# RTC.net
KiCad netlist of a schematic drawn in Altium Designer
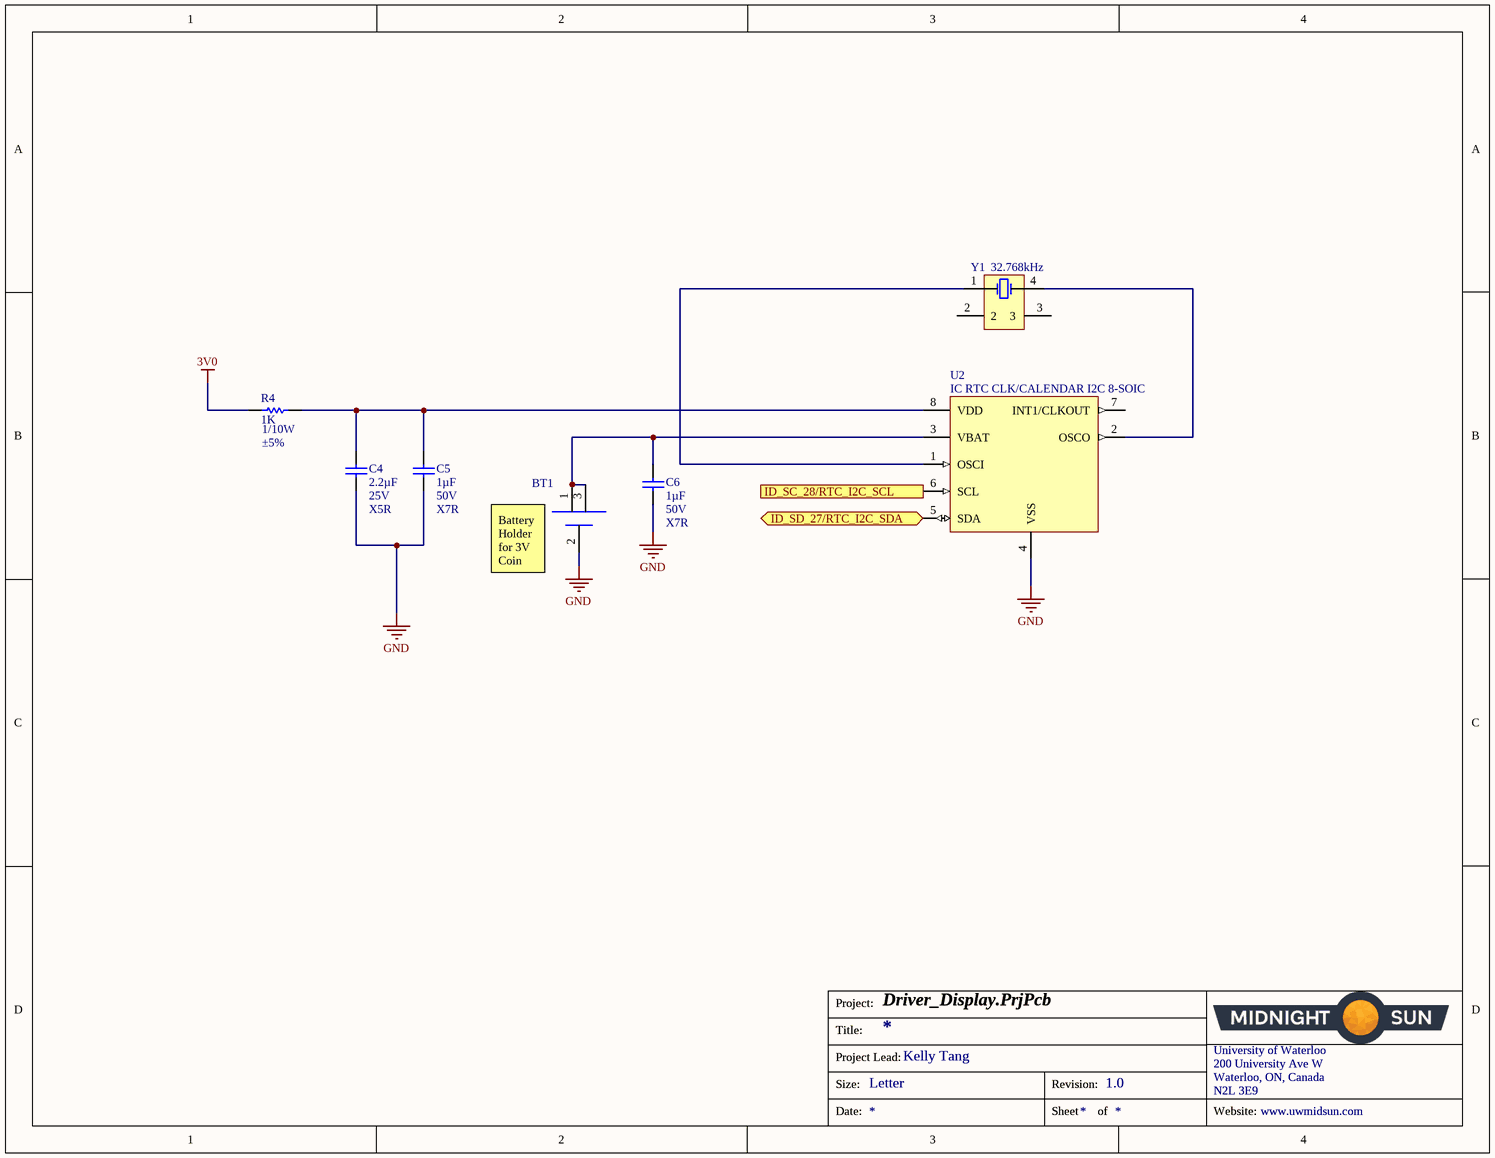
[diagram p0: RTC.SchDoc]

(export (version "E")
  (design (tool "Eeschema 10.0.6"))
  (components
    (comp (ref "BT1")
      (value "HOLDER BATTERY COIN 12MM DIA")
      (footprint "HOLDER COIN CELL 1220 3V")
      (description "Coin cell holder smd")
      (fields
        (field (name "MANUFACTURER") "Keystone Electronics")
        (field (name "MANUFACTURER PART NUMBER") "3000")
      )
      (libsource (lib "Schematic Diagrams") (part "HOLDER BATTERY COIN 12MM DIA"))
    )
    (comp (ref "C4")
      (value "CAP CER 2.2UF 25V 10% X5R 0603")
      (footprint "CAP, 0603")
      (description "2.2µF ±10% 25V Ceramic Capacitor X5R 0603 (1608 Metric)")
      (fields
        (field (name "TOLERANCE") "±10%")
        (field (name "CAPACITANCE") "2.2µF")
        (field (name "VOLTAGE") "25V")
        (field (name "TEMPERATURE COEFFICIENT") "X5R")
      )
      (libsource (lib "Schematic Diagrams") (part "CAP CER 2.2UF 25V 10% X5R 0603"))
    )
    (comp (ref "C5")
      (value "CAP CER 1UF 50V 10% X7R 0603")
      (footprint "CAP, 0603")
      (description "1µF ±10% 50V Ceramic Capacitor X7R 0603 (1608 Metric)")
      (fields
        (field (name "TOLERANCE") "±10%")
        (field (name "CAPACITANCE") "1µF")
        (field (name "VOLTAGE") "50V")
        (field (name "TEMPERATURE COEFFICIENT") "X7R")
      )
      (libsource (lib "Schematic Diagrams") (part "CAP CER 1UF 50V 10% X7R 0603"))
    )
    (comp (ref "C6")
      (value "CAP CER 1UF 50V 10% X7R 0603")
      (footprint "CAP, 0603")
      (description "1µF ±10% 50V Ceramic Capacitor X7R 0603 (1608 Metric)")
      (fields
        (field (name "TOLERANCE") "±10%")
        (field (name "CAPACITANCE") "1µF")
        (field (name "VOLTAGE") "50V")
        (field (name "TEMPERATURE COEFFICIENT") "X7R")
      )
      (libsource (lib "Schematic Diagrams") (part "CAP CER 1UF 50V 10% X7R 0603"))
    )
    (comp (ref "R4")
      (value "1K")
      (footprint "RES, 0603")
      (description "1k Ohm ±5% 0.1W, 1/10W Chip Resistor 0603 (1608 Metric)")
      (fields
        (field (name "MANUFACTURER") "Yageo")
        (field (name "MANUFACTURER PART NUMBER") "RC0603JR-071KL")
        (field (name "TOLERANCE") "±5%")
        (field (name "POWER (WATTS)") "1/10W")
      )
      (libsource (lib "Schematic Diagrams") (part "RES 1K OHM 5% 1/10W 0603"))
    )
    (comp (ref "U2")
      (value "IC RTC CLK/CALENDAR I2C 8-SOIC")
      (footprint "SOIC8")
      (description "Real Time Clock (RTC) IC Clock/Calendar I²C, 2-Wire Serial 8-SOIC (0.154\", 3.90mm Width)")
      (fields
        (field (name "MANUFACTURER") "NXP Semiconductors")
        (field (name "MANUFACTURER PART NUMBER") "PCF8523T/1,118")
      )
      (libsource (lib "Schematic Diagrams") (part "IC RTC CLK/CALENDAR I2C 8-SOIC"))
    )
    (comp (ref "Y1")
      (value "CRYSTAL 32.7680KHZ 12.5PF SMD")
      (footprint "4-SOJ")
      (description "32.768kHz ±20ppm Crystal 12.5pF 50 kOhms 4-SOJ, 5.50mm pitch")
      (fields
        (field (name "MANUFACTURER") "ECS International")
        (field (name "MANUFACTURER PART NUMBER") "ECS-.327-12.5-17X-TR")
        (field (name "FREQUENCY") "32.768kHz")
      )
      (libsource (lib "Schematic Diagrams") (part "CRYSTAL 32.7680KHZ 12.5PF SMD"))
    )
  )
  (nets
    (net (code "1") (name "/ID_SC_28{slash}RTC_I2C_SCL") (class "Default")
      (node (ref "U2") (pin "6") (pinfunction "SCL_6") (pintype "input"))
    )
    (net (code "2") (name "/ID_SD_27{slash}RTC_I2C_SDA") (class "Default")
      (node (ref "U2") (pin "5") (pinfunction "SDA_5") (pintype "bidirectional"))
    )
    (net (code "3") (name "3V0") (class "Default")
      (node (ref "R4") (pin "1") (pinfunction "1_1") (pintype "passive"))
    )
    (net (code "4") (name "GND") (class "Default")
      (node (ref "BT1") (pin "2") (pinfunction "negative_2") (pintype "power_in"))
      (node (ref "C4") (pin "2") (pinfunction "2_2") (pintype "passive"))
      (node (ref "C5") (pin "2") (pinfunction "2_2") (pintype "passive"))
      (node (ref "C6") (pin "2") (pinfunction "2_2") (pintype "passive"))
      (node (ref "U2") (pin "4") (pinfunction "VSS_4") (pintype "passive"))
    )
    (net (code "5") (name "Net-(BT1-positive_1)") (class "Default")
      (node (ref "BT1") (pin "1") (pinfunction "positive_1_1") (pintype "power_in"))
      (node (ref "BT1") (pin "3") (pinfunction "positive_2_3") (pintype "power_in"))
      (node (ref "C6") (pin "1") (pinfunction "1_1") (pintype "passive"))
      (node (ref "U2") (pin "3") (pinfunction "VBAT_3") (pintype "power_in"))
    )
    (net (code "6") (name "Net-(U2-OSCI)") (class "Default")
      (node (ref "U2") (pin "1") (pinfunction "OSCI_1") (pintype "input"))
      (node (ref "Y1") (pin "1") (pinfunction "1_1") (pintype "passive"))
    )
    (net (code "7") (name "Net-(U2-OSCO)") (class "Default")
      (node (ref "U2") (pin "2") (pinfunction "OSCO_2") (pintype "output"))
      (node (ref "Y1") (pin "4") (pinfunction "4_4") (pintype "passive"))
    )
    (net (code "8") (name "Net-(U2-VDD)") (class "Default")
      (node (ref "C4") (pin "1") (pinfunction "1_1") (pintype "passive"))
      (node (ref "C5") (pin "1") (pinfunction "1_1") (pintype "passive"))
      (node (ref "R4") (pin "2") (pinfunction "2_2") (pintype "passive"))
      (node (ref "U2") (pin "8") (pinfunction "VDD_8") (pintype "power_in"))
    )
    (net (code "9") (name "unconnected-(U2-INT1{slash}CLKOUT-Pad7)") (class "Default")
      (node (ref "U2") (pin "7") (pinfunction "INT1/CLKOUT_7") (pintype "output"))
    )
    (net (code "10") (name "unconnected-(Y1-Pad2)") (class "Default")
      (node (ref "Y1") (pin "2") (pinfunction "2_2") (pintype "passive"))
    )
    (net (code "11") (name "unconnected-(Y1-Pad3)") (class "Default")
      (node (ref "Y1") (pin "3") (pinfunction "3_3") (pintype "passive"))
    )
  )
)
